# main.net
KiCad netlist of a schematic drawn in Altium Designer
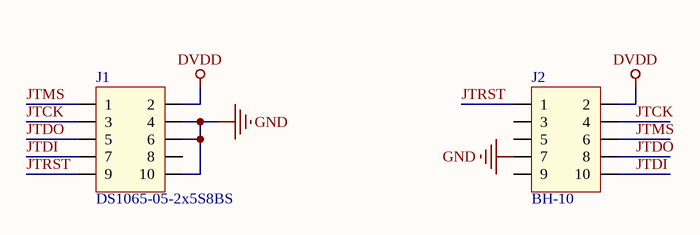
[diagram p0: main.SchDoc]

(export (version "E")
  (design (tool "Eeschema 10.0.6"))
  (components
    (comp (ref "J1")
      (value "DS1065-05-2x5S8BS")
      (footprint "DS1065-05-2x5S8BS")
      (libsource (lib "LocalLib") (part "DS1065-05-2x5S8BS"))
    )
    (comp (ref "J2") (value "BH-10") (footprint "IDC-10-2.54") (libsource (lib "LocalLib") (part "BH-10")))
  )
  (nets
    (net (code "1") (name "/JTCK") (class "Default")
      (node (ref "J1") (pin "3") (pinfunction "3_3") (pintype "passive"))
      (node (ref "J2") (pin "4") (pinfunction "4_4") (pintype "passive"))
    )
    (net (code "2") (name "/JTDI") (class "Default")
      (node (ref "J1") (pin "7") (pinfunction "7_7") (pintype "passive"))
      (node (ref "J2") (pin "10") (pinfunction "10_10") (pintype "passive"))
    )
    (net (code "3") (name "/JTDO") (class "Default")
      (node (ref "J1") (pin "5") (pinfunction "5_5") (pintype "passive"))
      (node (ref "J2") (pin "8") (pinfunction "8_8") (pintype "passive"))
    )
    (net (code "4") (name "/JTMS") (class "Default")
      (node (ref "J1") (pin "1") (pinfunction "1_1") (pintype "passive"))
      (node (ref "J2") (pin "6") (pinfunction "6_6") (pintype "passive"))
    )
    (net (code "5") (name "/JTRST") (class "Default")
      (node (ref "J1") (pin "9") (pinfunction "9_9") (pintype "passive"))
      (node (ref "J2") (pin "1") (pinfunction "1_1") (pintype "passive"))
    )
    (net (code "6") (name "DVDD") (class "Default")
      (node (ref "J1") (pin "2") (pinfunction "2_2") (pintype "passive"))
      (node (ref "J2") (pin "2") (pinfunction "2_2") (pintype "passive"))
    )
    (net (code "7") (name "GND") (class "Default")
      (node (ref "J1") (pin "10") (pinfunction "10_10") (pintype "passive"))
      (node (ref "J1") (pin "4") (pinfunction "4_4") (pintype "passive"))
      (node (ref "J1") (pin "6") (pinfunction "6_6") (pintype "passive"))
      (node (ref "J2") (pin "7") (pinfunction "7_7") (pintype "passive"))
    )
    (net (code "8") (name "unconnected-(J1-Pad8)") (class "Default")
      (node (ref "J1") (pin "8") (pinfunction "8_8") (pintype "passive"))
    )
    (net (code "9") (name "unconnected-(J2-Pad3)") (class "Default")
      (node (ref "J2") (pin "3") (pinfunction "3_3") (pintype "passive"))
    )
    (net (code "10") (name "unconnected-(J2-Pad5)") (class "Default")
      (node (ref "J2") (pin "5") (pinfunction "5_5") (pintype "passive"))
    )
    (net (code "11") (name "unconnected-(J2-Pad9)") (class "Default")
      (node (ref "J2") (pin "9") (pinfunction "9_9") (pintype "passive"))
    )
  )
)
